# drawdio.net
KiCad netlist of a schematic drawn in EAGLE
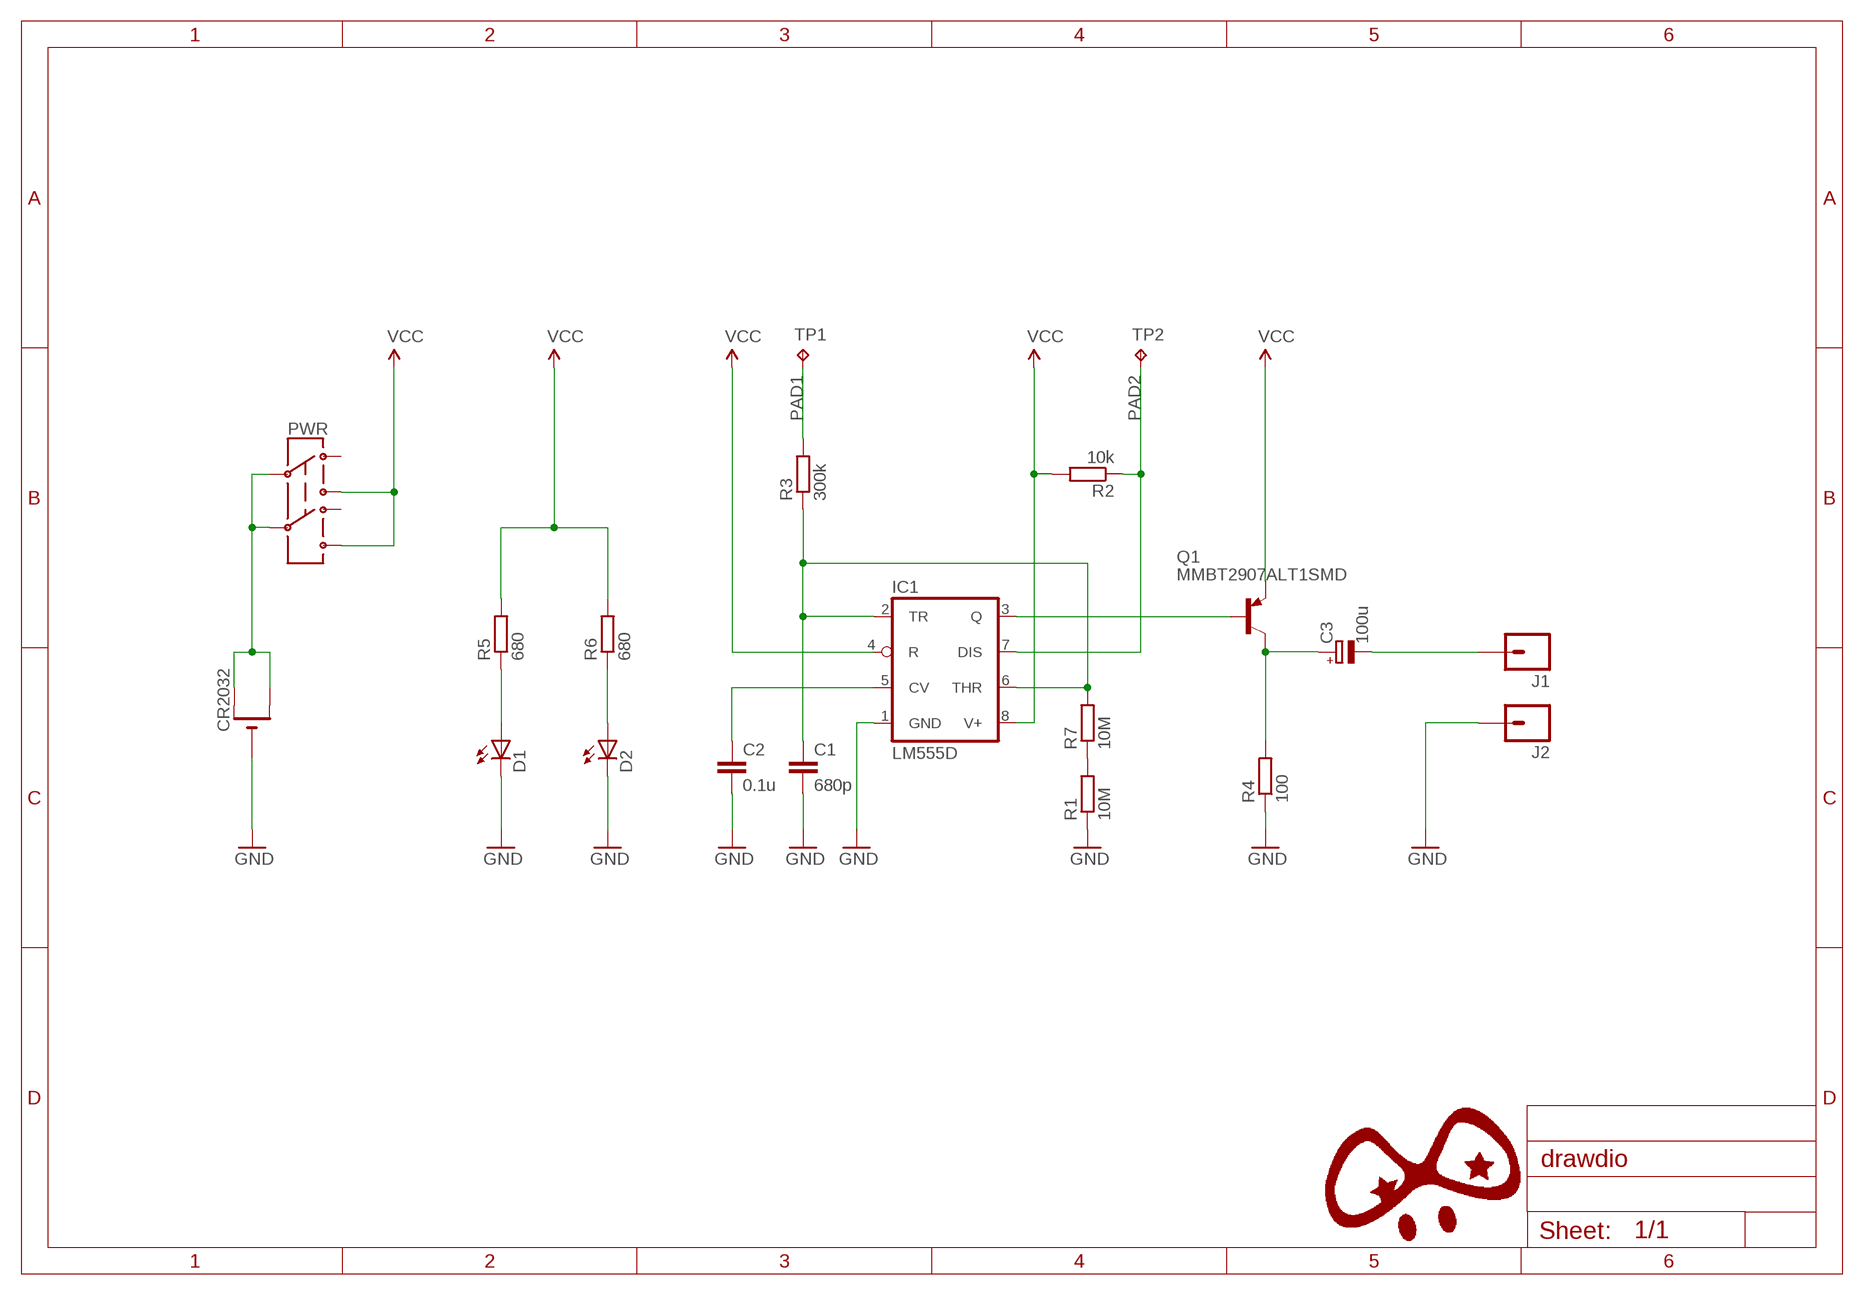
[diagram p0: schematic, sheet 1]

(export (version "E")
  (design (tool "Eeschema 10.0.6"))
  (components
    (comp (ref "C1")
      (value "680p")
      (footprint "eagle-import:C1206K")
      (libsource (lib "eagle-import") (part "C-EUC1206K"))
    )
    (comp (ref "C2")
      (value "0.1u")
      (footprint "eagle-import:C1206K")
      (libsource (lib "eagle-import") (part "C-EUC1206K"))
    )
    (comp (ref "C3")
      (value "100u")
      (footprint "eagle-import:153CLV-0605")
      (libsource (lib "eagle-import") (part "CPOL-EU153CLV-0605"))
    )
    (comp (ref "CR2032")
      (value "CR2032THM")
      (footprint "eagle-import:CR2032-THRU")
      (libsource (lib "eagle-import") (part "CR2032THM"))
    )
    (comp (ref "D1")
      (value "LED-1206")
      (footprint "eagle-import:C1206")
      (libsource (lib "eagle-import") (part "LED-1206"))
    )
    (comp (ref "D2")
      (value "LED-1206")
      (footprint "eagle-import:C1206")
      (libsource (lib "eagle-import") (part "LED-1206"))
    )
    (comp (ref "IC1")
      (value "LM555D")
      (footprint "eagle-import:SO08")
      (libsource (lib "eagle-import") (part "555DLM"))
    )
    (comp (ref "J1")
      (value "M01NOSILK-KIT")
      (footprint "eagle-import:1X01NS-KIT")
      (libsource (lib "eagle-import") (part "M01NOSILK-KIT"))
    )
    (comp (ref "J2")
      (value "M01NOSILK-KIT")
      (footprint "eagle-import:1X01NS-KIT")
      (libsource (lib "eagle-import") (part "M01NOSILK-KIT"))
    )
    (comp (ref "PWR")
      (value "SWITCH-DPDTOS")
      (footprint "eagle-import:OS")
      (libsource (lib "eagle-import") (part "SWITCH-DPDTOS"))
    )
    (comp (ref "Q1")
      (value "MMBT2907ALT1SMD")
      (footprint "eagle-import:SOT23-BEC")
      (libsource (lib "eagle-import") (part "MMBT2907SMDALT1"))
    )
    (comp (ref "R1")
      (value "10M")
      (footprint "eagle-import:R1206W")
      (libsource (lib "eagle-import") (part "R-EU_R1206W"))
    )
    (comp (ref "R2")
      (value "10k")
      (footprint "eagle-import:R1206W")
      (libsource (lib "eagle-import") (part "R-EU_R1206W"))
    )
    (comp (ref "R3")
      (value "300k")
      (footprint "eagle-import:R1206W")
      (libsource (lib "eagle-import") (part "R-EU_R1206W"))
    )
    (comp (ref "R4")
      (value "100")
      (footprint "eagle-import:R1206W")
      (libsource (lib "eagle-import") (part "R-EU_R1206W"))
    )
    (comp (ref "R5")
      (value "680")
      (footprint "eagle-import:R1206W")
      (libsource (lib "eagle-import") (part "R-EU_R1206W"))
    )
    (comp (ref "R6")
      (value "680")
      (footprint "eagle-import:R1206W")
      (libsource (lib "eagle-import") (part "R-EU_R1206W"))
    )
    (comp (ref "R7")
      (value "10M")
      (footprint "eagle-import:R1206W")
      (libsource (lib "eagle-import") (part "R-EU_R1206W"))
    )
    (comp (ref "TP1")
      (value "TPB2,54")
      (footprint "eagle-import:B2,54")
      (libsource (lib "eagle-import") (part "TPB2,54"))
    )
    (comp (ref "TP2")
      (value "TPB2,54")
      (footprint "eagle-import:B2,54")
      (libsource (lib "eagle-import") (part "TPB2,54"))
    )
  )
  (nets
    (net (code "1") (name "/PAD1") (class "Default")
      (node (ref "R3") (pin "2") (pinfunction "2_2") (pintype "passive"))
      (node (ref "TP1") (pin "TP") (pinfunction "TP_TP") (pintype "input"))
    )
    (net (code "2") (name "/PAD2") (class "Default")
      (node (ref "IC1") (pin "7") (pinfunction "DIS_7") (pintype "input"))
      (node (ref "R2") (pin "1") (pinfunction "1_1") (pintype "passive"))
      (node (ref "TP2") (pin "TP") (pinfunction "TP_TP") (pintype "input"))
    )
    (net (code "3") (name "GND") (class "Default")
      (node (ref "C1") (pin "2") (pinfunction "2_2") (pintype "passive"))
      (node (ref "C2") (pin "2") (pinfunction "2_2") (pintype "passive"))
      (node (ref "CR2032") (pin "-") (pinfunction "-_-") (pintype "passive"))
      (node (ref "D1") (pin "C") (pinfunction "C_C") (pintype "passive"))
      (node (ref "D2") (pin "C") (pinfunction "C_C") (pintype "passive"))
      (node (ref "IC1") (pin "1") (pinfunction "GND_1") (pintype "power_in"))
      (node (ref "J2") (pin "1") (pinfunction "1_1") (pintype "passive"))
      (node (ref "R1") (pin "1") (pinfunction "1_1") (pintype "passive"))
      (node (ref "R4") (pin "1") (pinfunction "1_1") (pintype "passive"))
    )
    (net (code "4") (name "Net-(C3-Pad+)") (class "Default")
      (node (ref "C3") (pin "+") (pinfunction "+_+") (pintype "passive"))
      (node (ref "Q1") (pin "C") (pinfunction "C_C") (pintype "passive"))
      (node (ref "R4") (pin "2") (pinfunction "2_2") (pintype "passive"))
    )
    (net (code "5") (name "Net-(C3-Pad-)") (class "Default")
      (node (ref "C3") (pin "-") (pinfunction "-_-") (pintype "passive"))
      (node (ref "J1") (pin "1") (pinfunction "1_1") (pintype "passive"))
    )
    (net (code "6") (name "Net-(CR2032-+)") (class "Default")
      (node (ref "CR2032") (pin "+1") (pinfunction "+_+1") (pintype "passive"))
      (node (ref "CR2032") (pin "+2") (pinfunction "+1_+2") (pintype "passive"))
      (node (ref "PWR") (pin "2") (pinfunction "2_2") (pintype "bidirectional"))
      (node (ref "PWR") (pin "5") (pinfunction "5_5") (pintype "bidirectional"))
    )
    (net (code "7") (name "Net-(D1-PadA)") (class "Default")
      (node (ref "D1") (pin "A") (pinfunction "A_A") (pintype "passive"))
      (node (ref "R5") (pin "1") (pinfunction "1_1") (pintype "passive"))
    )
    (net (code "8") (name "Net-(D2-PadA)") (class "Default")
      (node (ref "D2") (pin "A") (pinfunction "A_A") (pintype "passive"))
      (node (ref "R6") (pin "1") (pinfunction "1_1") (pintype "passive"))
    )
    (net (code "9") (name "Net-(IC1-CV)") (class "Default")
      (node (ref "C2") (pin "1") (pinfunction "1_1") (pintype "passive"))
      (node (ref "IC1") (pin "5") (pinfunction "CV_5") (pintype "input"))
    )
    (net (code "10") (name "Net-(IC1-Q)") (class "Default")
      (node (ref "IC1") (pin "3") (pinfunction "Q_3") (pintype "output"))
      (node (ref "Q1") (pin "B") (pinfunction "B_B") (pintype "passive"))
    )
    (net (code "11") (name "Net-(IC1-THR)") (class "Default")
      (node (ref "C1") (pin "1") (pinfunction "1_1") (pintype "passive"))
      (node (ref "IC1") (pin "2") (pinfunction "TR_2") (pintype "input"))
      (node (ref "IC1") (pin "6") (pinfunction "THR_6") (pintype "input"))
      (node (ref "R3") (pin "1") (pinfunction "1_1") (pintype "passive"))
      (node (ref "R7") (pin "2") (pinfunction "2_2") (pintype "passive"))
    )
    (net (code "12") (name "Net-(R1-Pad2)") (class "Default")
      (node (ref "R1") (pin "2") (pinfunction "2_2") (pintype "passive"))
      (node (ref "R7") (pin "1") (pinfunction "1_1") (pintype "passive"))
    )
    (net (code "13") (name "VCC") (class "Default")
      (node (ref "IC1") (pin "4") (pinfunction "R_4") (pintype "input"))
      (node (ref "IC1") (pin "8") (pinfunction "V+_8") (pintype "power_in"))
      (node (ref "PWR") (pin "3") (pinfunction "3_3") (pintype "bidirectional"))
      (node (ref "PWR") (pin "6") (pinfunction "6_6") (pintype "bidirectional"))
      (node (ref "Q1") (pin "E") (pinfunction "E_E") (pintype "passive"))
      (node (ref "R2") (pin "2") (pinfunction "2_2") (pintype "passive"))
      (node (ref "R5") (pin "2") (pinfunction "2_2") (pintype "passive"))
      (node (ref "R6") (pin "2") (pinfunction "2_2") (pintype "passive"))
    )
    (net (code "14") (name "unconnected-(PWR-Pad1)") (class "Default")
      (node (ref "PWR") (pin "1") (pinfunction "1_1") (pintype "bidirectional"))
    )
    (net (code "15") (name "unconnected-(PWR-Pad4)") (class "Default")
      (node (ref "PWR") (pin "4") (pinfunction "4_4") (pintype "bidirectional"))
    )
  )
)
